# 1WireStamp-V02-bigger-Footprint-008.net
KiCad netlist of a schematic drawn in EAGLE
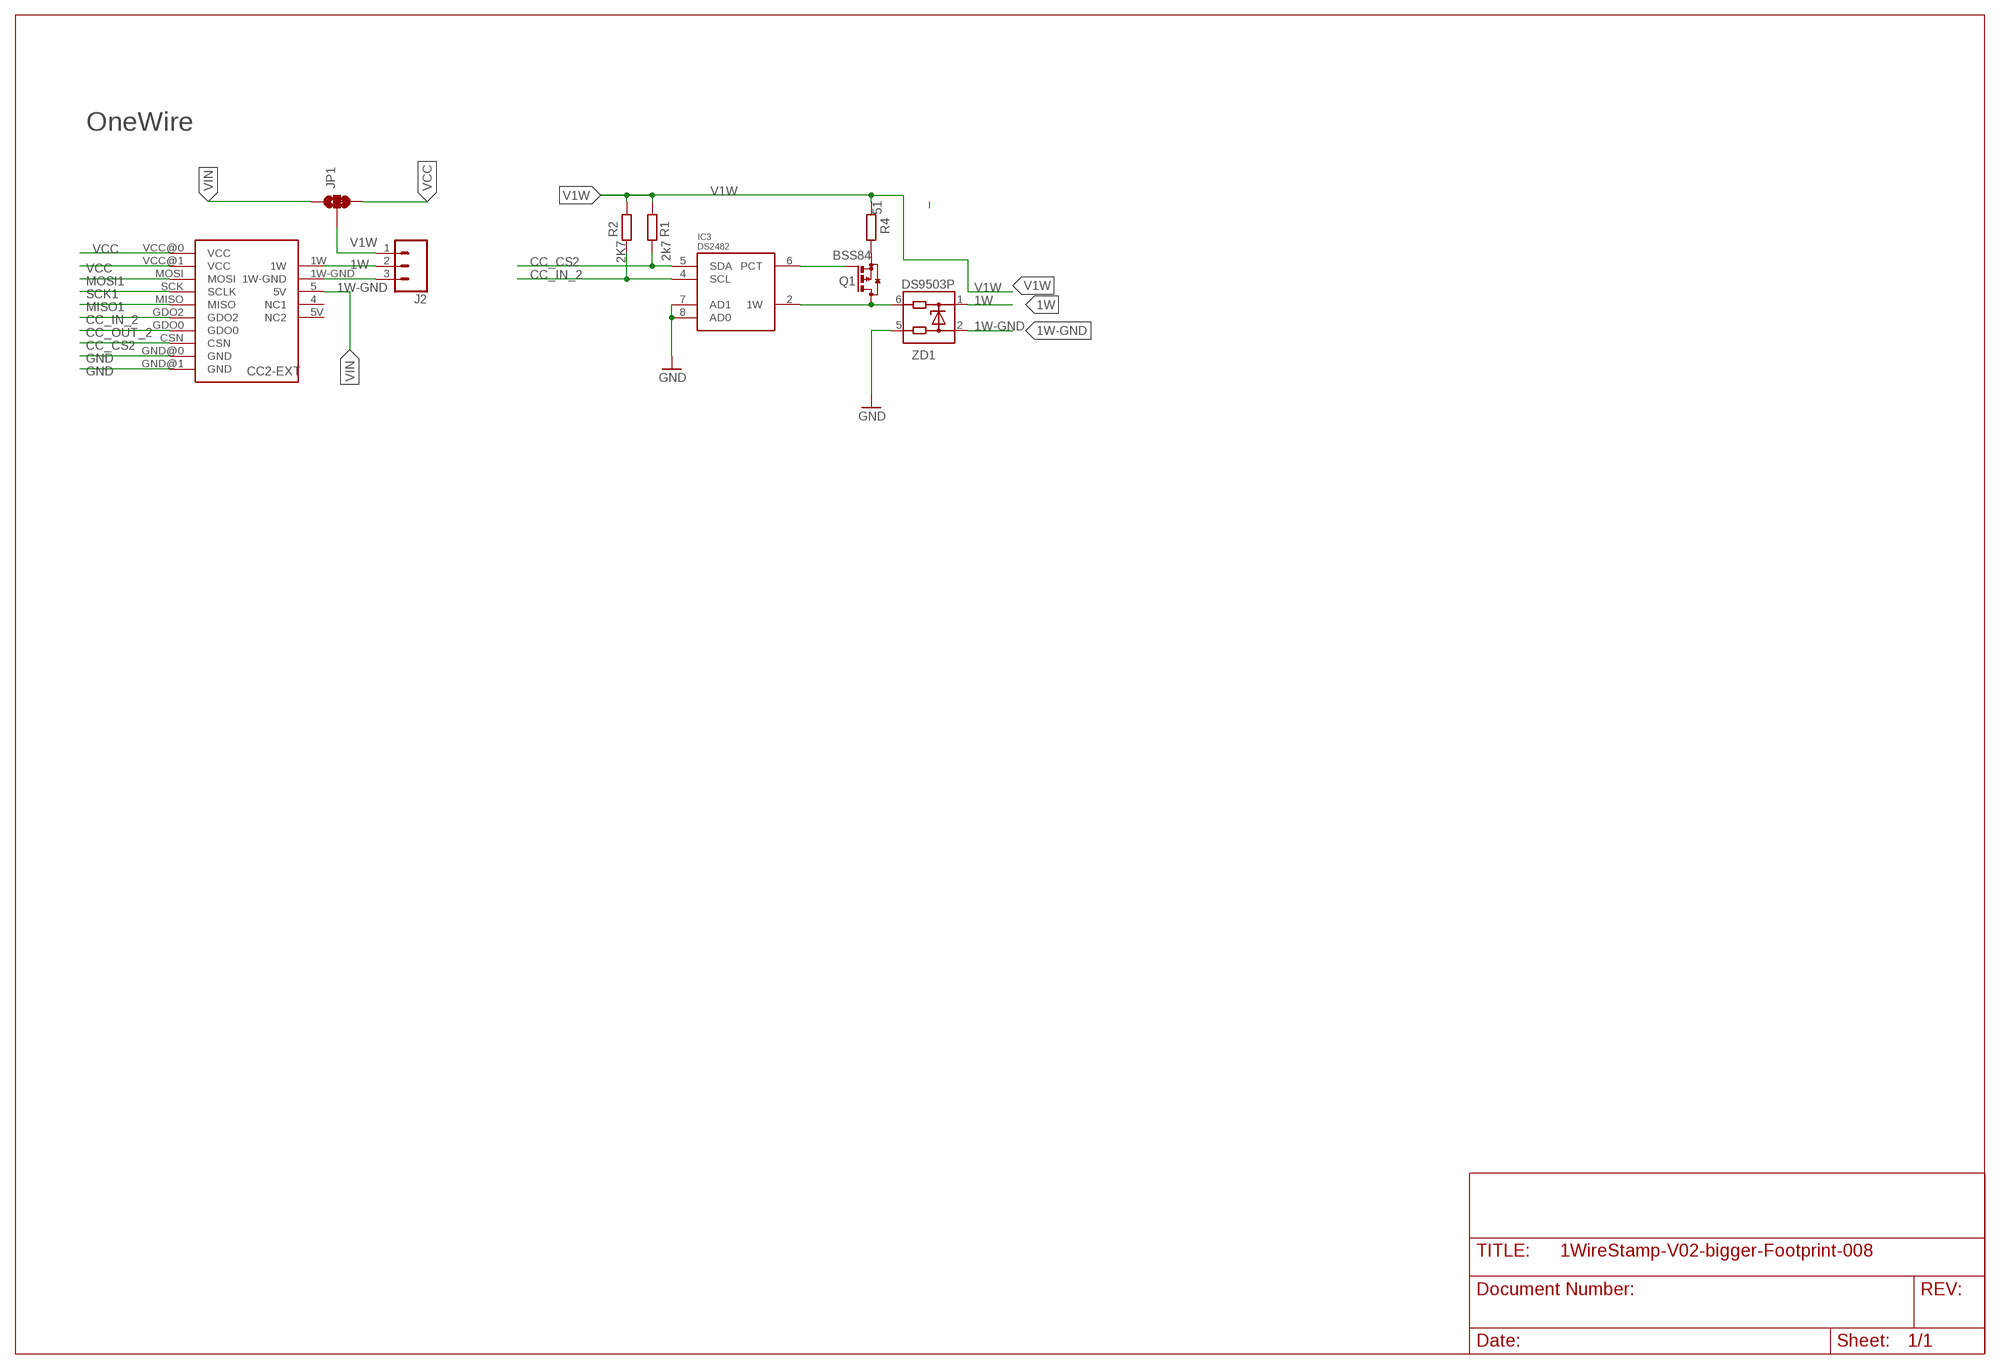
[diagram p0: schematic, sheet 1]

(export (version "E")
  (design (tool "Eeschema 10.0.6"))
  (components
    (comp (ref "CC2-EXT")
      (value "ONEWIRE-MODULEONEWIRE_CC1101_WO-SILK")
      (footprint "eagle-import:ONEWIRE_CC1101_MOD_WO_SILK")
      (libsource (lib "eagle-import") (part "ONEWIRE-MODULEONEWIRE_CC1101_WO-SILK"))
    )
    (comp (ref "IC3")
      (value "DS2482")
      (footprint "eagle-import:SO08")
      (libsource (lib "eagle-import") (part "DS2482-100S"))
    )
    (comp (ref "J2")
      (value "CONN_03LONGPADS")
      (footprint "eagle-import:1X03_LONGPADS")
      (libsource (lib "eagle-import") (part "CONN_03LONGPADS"))
    )
    (comp (ref "JP1")
      (value "JUMPER-SMT_3_1-NC_TRACE_SILK")
      (footprint "eagle-import:SMT-JUMPER_3_1-NC_TRACE_SILK")
      (libsource (lib "eagle-import") (part "JUMPER-SMT_3_1-NC_TRACE_SILK"))
    )
    (comp (ref "Q1")
      (value "BSS84")
      (footprint "eagle-import:SOT23")
      (libsource (lib "eagle-import") (part "BSS84"))
    )
    (comp (ref "R1")
      (value "2k7")
      (footprint "eagle-import:R0805")
      (libsource (lib "eagle-import") (part "R-EU_R0805"))
    )
    (comp (ref "R2")
      (value "2K7")
      (footprint "eagle-import:R0805")
      (libsource (lib "eagle-import") (part "R-EU_R0805"))
    )
    (comp (ref "R4")
      (value "51")
      (footprint "eagle-import:R0805")
      (libsource (lib "eagle-import") (part "R-EU_R0805"))
    )
    (comp (ref "ZD1")
      (value "DS9503P")
      (footprint "eagle-import:TSOC6")
      (libsource (lib "eagle-import") (part "DS9503P"))
    )
  )
  (nets
    (net (code "1") (name "/CC_CS2") (class "Default")
      (node (ref "CC2-EXT") (pin "CSN") (pinfunction "CSN_CSN") (pintype "bidirectional"))
      (node (ref "IC3") (pin "5") (pinfunction "SDA_5") (pintype "bidirectional"))
      (node (ref "R1") (pin "2") (pinfunction "2_2") (pintype "passive"))
    )
    (net (code "2") (name "/CC_IN_2") (class "Default")
      (node (ref "CC2-EXT") (pin "GDO2") (pinfunction "GDO2_GDO2") (pintype "bidirectional"))
      (node (ref "IC3") (pin "4") (pinfunction "SCL_4") (pintype "input"))
      (node (ref "R2") (pin "2") (pinfunction "2_2") (pintype "passive"))
    )
    (net (code "3") (name "/CC_OUT_2") (class "Default")
      (node (ref "CC2-EXT") (pin "GDO0") (pinfunction "GDO0_GDO0") (pintype "bidirectional"))
    )
    (net (code "4") (name "/MISO1") (class "Default")
      (node (ref "CC2-EXT") (pin "MISO") (pinfunction "MISO_MISO") (pintype "bidirectional"))
    )
    (net (code "5") (name "/MOSI1") (class "Default")
      (node (ref "CC2-EXT") (pin "MOSI") (pinfunction "MOSI_MOSI") (pintype "bidirectional"))
    )
    (net (code "6") (name "/SCK1") (class "Default")
      (node (ref "CC2-EXT") (pin "SCK") (pinfunction "SCLK_SCK") (pintype "bidirectional"))
    )
    (net (code "7") (name "1W") (class "Default")
      (node (ref "CC2-EXT") (pin "1W") (pinfunction "1W_1W") (pintype "bidirectional"))
      (node (ref "J2") (pin "2") (pinfunction "2_2") (pintype "passive"))
      (node (ref "ZD1") (pin "1") (pinfunction "P$1_1") (pintype "passive"))
    )
    (net (code "8") (name "1W-GND") (class "Default")
      (node (ref "CC2-EXT") (pin "1W-GND") (pinfunction "1W-GND_1W-GND") (pintype "bidirectional"))
      (node (ref "J2") (pin "3") (pinfunction "3_3") (pintype "passive"))
      (node (ref "ZD1") (pin "2") (pinfunction "P$2_2") (pintype "passive"))
    )
    (net (code "9") (name "GND") (class "Default")
      (node (ref "CC2-EXT") (pin "GND@0") (pinfunction "GND_GND@0") (pintype "power_in"))
      (node (ref "CC2-EXT") (pin "GND@1") (pinfunction "GND_GND@1") (pintype "power_in"))
      (node (ref "IC3") (pin "7") (pinfunction "AD1_7") (pintype "input"))
      (node (ref "IC3") (pin "8") (pinfunction "AD0_8") (pintype "input"))
      (node (ref "ZD1") (pin "5") (pinfunction "P$3_5") (pintype "passive"))
    )
    (net (code "10") (name "Net-(IC3A-1W)") (class "Default")
      (node (ref "IC3") (pin "2") (pinfunction "1W_2") (pintype "open_collector"))
      (node (ref "Q1") (pin "3") (pinfunction "D_3") (pintype "passive"))
      (node (ref "ZD1") (pin "6") (pinfunction "P$4_6") (pintype "passive"))
    )
    (net (code "11") (name "Net-(IC3A-PCT)") (class "Default")
      (node (ref "IC3") (pin "6") (pinfunction "PCT_6") (pintype "output"))
      (node (ref "Q1") (pin "1") (pinfunction "G_1") (pintype "passive"))
    )
    (net (code "12") (name "Net-(Q1-S)") (class "Default")
      (node (ref "Q1") (pin "2") (pinfunction "S_2") (pintype "passive"))
      (node (ref "R4") (pin "1") (pinfunction "1_1") (pintype "passive"))
    )
    (net (code "13") (name "V1W") (class "Default")
      (node (ref "J2") (pin "1") (pinfunction "1_1") (pintype "passive"))
      (node (ref "JP1") (pin "2") (pinfunction "2_2") (pintype "passive"))
      (node (ref "R1") (pin "1") (pinfunction "1_1") (pintype "passive"))
      (node (ref "R2") (pin "1") (pinfunction "1_1") (pintype "passive"))
      (node (ref "R4") (pin "2") (pinfunction "2_2") (pintype "passive"))
    )
    (net (code "14") (name "VCC") (class "Default")
      (node (ref "CC2-EXT") (pin "VCC@0") (pinfunction "VCC_VCC@0") (pintype "power_in"))
      (node (ref "CC2-EXT") (pin "VCC@1") (pinfunction "VCC_VCC@1") (pintype "power_in"))
      (node (ref "JP1") (pin "3") (pinfunction "3_3") (pintype "passive"))
    )
    (net (code "15") (name "VIN") (class "Default")
      (node (ref "CC2-EXT") (pin "5") (pinfunction "5V_5") (pintype "bidirectional"))
      (node (ref "JP1") (pin "1") (pinfunction "1_1") (pintype "passive"))
    )
    (net (code "16") (name "unconnected-(CC2-EXT-NC1-Pad4)") (class "Default")
      (node (ref "CC2-EXT") (pin "4") (pinfunction "NC1_4") (pintype "bidirectional"))
    )
    (net (code "17") (name "unconnected-(CC2-EXT-NC2-Pad5V)") (class "Default")
      (node (ref "CC2-EXT") (pin "5V") (pinfunction "NC2_5V") (pintype "bidirectional"))
    )
  )
)
